# Sensors.net
KiCad netlist of a schematic drawn in Altium Designer
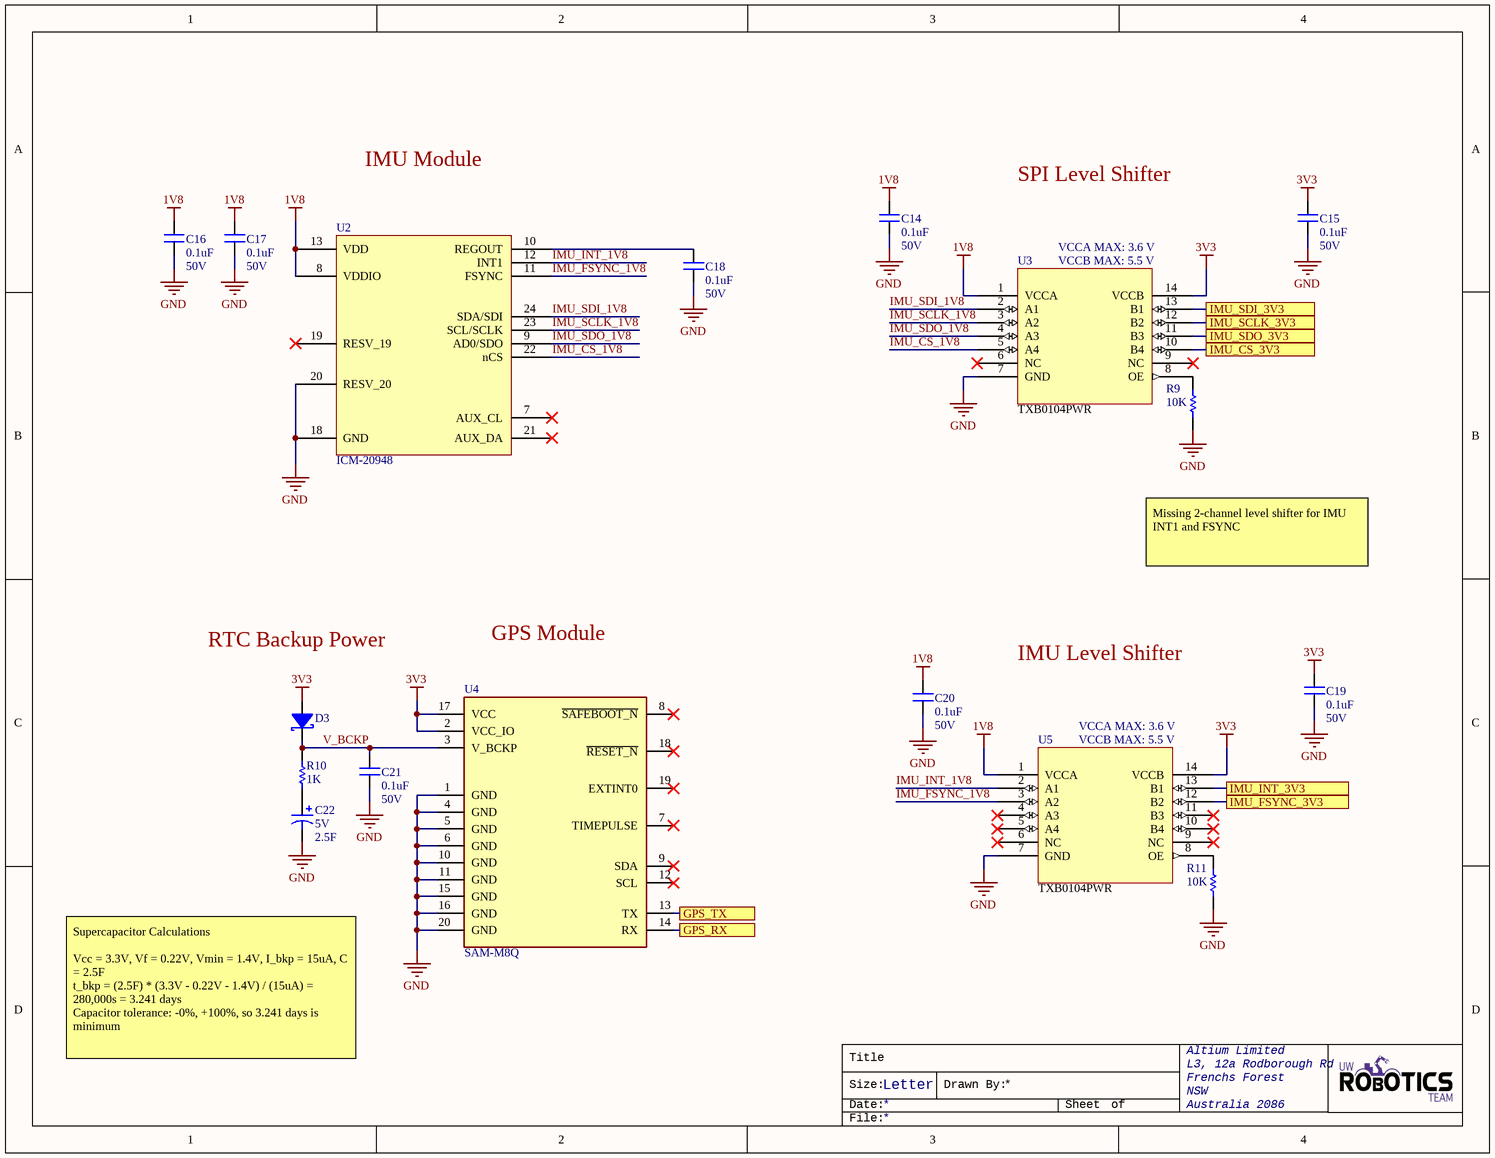
[diagram p0: Sensors.SchDoc]

(export (version "E")
  (design (tool "Eeschema 10.0.6"))
  (components
    (comp (ref "C14")
      (value "0.1uF")
      (footprint "CAPC2012X140N")
      (description "CAP CER 0.1UF 50V X7R 0805")
      (fields
        (field (name "TOLERANCE") "10%")
        (field (name "VOLTAGE RATING") "50V")
        (field (name "Comment") "CAP_0.1uF_50V_0805")
      )
      (libsource (lib "UWRT_Schematic_Library_2020") (part "CAP_0.1uF_50V_0805"))
    )
    (comp (ref "C15")
      (value "0.1uF")
      (footprint "CAPC2012X140N")
      (description "CAP CER 0.1UF 50V X7R 0805")
      (fields
        (field (name "TOLERANCE") "10%")
        (field (name "VOLTAGE RATING") "50V")
        (field (name "Comment") "CAP_0.1uF_50V_0805")
      )
      (libsource (lib "UWRT_Schematic_Library_2020") (part "CAP_0.1uF_50V_0805"))
    )
    (comp (ref "C16")
      (value "0.1uF")
      (footprint "CAPC2012X140N")
      (description "CAP CER 0.1UF 50V X7R 0805")
      (fields
        (field (name "TOLERANCE") "10%")
        (field (name "VOLTAGE RATING") "50V")
        (field (name "Comment") "CAP_0.1uF_50V_0805")
      )
      (libsource (lib "UWRT_Schematic_Library_2020") (part "CAP_0.1uF_50V_0805"))
    )
    (comp (ref "C17")
      (value "0.1uF")
      (footprint "CAPC2012X140N")
      (description "CAP CER 0.1UF 50V X7R 0805")
      (fields
        (field (name "TOLERANCE") "10%")
        (field (name "VOLTAGE RATING") "50V")
        (field (name "Comment") "CAP_0.1uF_50V_0805")
      )
      (libsource (lib "UWRT_Schematic_Library_2020") (part "CAP_0.1uF_50V_0805"))
    )
    (comp (ref "C18")
      (value "0.1uF")
      (footprint "CAPC2012X140N")
      (description "CAP CER 0.1UF 50V X7R 0805")
      (fields
        (field (name "TOLERANCE") "10%")
        (field (name "VOLTAGE RATING") "50V")
        (field (name "Comment") "CAP_0.1uF_50V_0805")
      )
      (libsource (lib "UWRT_Schematic_Library_2020") (part "CAP_0.1uF_50V_0805"))
    )
    (comp (ref "C19")
      (value "0.1uF")
      (footprint "CAPC2012X140N")
      (description "CAP CER 0.1UF 50V X7R 0805")
      (fields
        (field (name "TOLERANCE") "10%")
        (field (name "VOLTAGE RATING") "50V")
        (field (name "Comment") "CAP_0.1uF_50V_0805")
      )
      (libsource (lib "UWRT_Schematic_Library_2020") (part "CAP_0.1uF_50V_0805"))
    )
    (comp (ref "C20")
      (value "0.1uF")
      (footprint "CAPC2012X140N")
      (description "CAP CER 0.1UF 50V X7R 0805")
      (fields
        (field (name "TOLERANCE") "10%")
        (field (name "VOLTAGE RATING") "50V")
        (field (name "Comment") "CAP_0.1uF_50V_0805")
      )
      (libsource (lib "UWRT_Schematic_Library_2020") (part "CAP_0.1uF_50V_0805"))
    )
    (comp (ref "C21")
      (value "0.1uF")
      (footprint "CAPC2012X140N")
      (description "CAP CER 0.1UF 50V X7R 0805")
      (fields
        (field (name "TOLERANCE") "10%")
        (field (name "VOLTAGE RATING") "50V")
        (field (name "Comment") "CAP_0.1uF_50V_0805")
      )
      (libsource (lib "UWRT_Schematic_Library_2020") (part "CAP_0.1uF_50V_0805"))
    )
    (comp (ref "C22")
      (value "CAP_2.5F_5V")
      (description "CAP 2.5F 5V")
      (fields
        (field (name "TOLERANCE") "0%, +100%")
        (field (name "VOLTAGE RATING") "5V")
        (field (name "CAPACITANCE") "2.5F")
      )
      (libsource (lib "UWRT_Schematic_Library_2020") (part "CAP_2.5F_5V"))
    )
    (comp (ref "D3")
      (value "DIO_SCHOTTKY_30V_800mA")
      (footprint "DIO_CUS520,H3F")
      (description "DIODE SCHOTTKY 30V 800MA USC")
      (libsource (lib "UWRT_Schematic_Library_2020") (part "DIO_SCHOTTKY_30V_800mA"))
    )
    (comp (ref "R9")
      (value "10K")
      (footprint "RESC0603(1608)_N")
      (description "RES SMD 10K OHM 5% 1/10W 0603")
      (fields (field (name "TOLERANCE") "5%") (field (name "Comment") "RES_10K_0603"))
      (libsource (lib "UWRT_Schematic_Library_2020") (part "RES_10K_0603"))
    )
    (comp (ref "R10")
      (value "1K")
      (footprint "RESC0603(1608)_N")
      (description "RES SMD 1K OHM 5% 1/10W 0603")
      (fields (field (name "TOLERANCE") "5%") (field (name "Comment") "RES_1K_0603"))
      (libsource (lib "UWRT_Schematic_Library_2020") (part "RES_1K_0603"))
    )
    (comp (ref "R11")
      (value "10K")
      (footprint "RESC0603(1608)_N")
      (description "RES SMD 10K OHM 5% 1/10W 0603")
      (fields (field (name "TOLERANCE") "5%") (field (name "Comment") "RES_10K_0603"))
      (libsource (lib "UWRT_Schematic_Library_2020") (part "RES_10K_0603"))
    )
    (comp (ref "U2")
      (value "IC_9DOF_IMU")
      (footprint "ICM-20948")
      (description "IMU ACCEL/GYRO/COMPI2C/SPI 24QFN")
      (fields
        (field (name "MANUFACTURER") "TDK InvenSense")
        (field (name "MANUFACTURER PART NUMBER") "ICM-20948")
      )
      (libsource (lib "UWRT_Schematic_Library_2020") (part "IC_9DOF_IMU"))
    )
    (comp (ref "U3")
      (value "TXB0104PWR")
      (footprint "UWRT_Footprint_Library_2020:PW14")
      (fields
        (field (name "MANUFACTURER_PART_NUMBER") "TXB0104PWR")
        (field (name "GENERIC_PART_NUMBER") "TXB0104")
        (field (name "MANUFACTURER") "Texas Instruments")
        (field (name "VCCB MAX") "VCCB MAX: 5.5 V")
        (field (name "VCCA MAX") "VCCA MAX: 3.6 V")
      )
      (libsource (lib "UWRT_Schematic_Library_2020") (part "IC_4CH_LVL_SHIFTER"))
    )
    (comp (ref "U4")
      (value "SAM-M8Q")
      (description "Rf Rx Galileo 1.575GHZ/1.602GHZ")
      (libsource (lib "UWRT_Schematic_Library_2020") (part "SAM-M8Q"))
    )
    (comp (ref "U5")
      (value "TXB0104PWR")
      (footprint "UWRT_Footprint_Library_2020:PW14")
      (fields
        (field (name "MANUFACTURER_PART_NUMBER") "TXB0104PWR")
        (field (name "GENERIC_PART_NUMBER") "TXB0104")
        (field (name "MANUFACTURER") "Texas Instruments")
        (field (name "VCCB MAX") "VCCB MAX: 5.5 V")
        (field (name "VCCA MAX") "VCCA MAX: 3.6 V")
      )
      (libsource (lib "UWRT_Schematic_Library_2020") (part "IC_4CH_LVL_SHIFTER"))
    )
  )
  (nets
    (net (code "1") (name "/GPS_RX") (class "Default")
      (node (ref "U4") (pin "14") (pinfunction "RX_14") (pintype "passive"))
    )
    (net (code "2") (name "/GPS_TX") (class "Default")
      (node (ref "U4") (pin "13") (pinfunction "TX_13") (pintype "passive"))
    )
    (net (code "3") (name "/IMU_CS_1V8") (class "Default")
      (node (ref "U2") (pin "22") (pinfunction "nCS_22") (pintype "passive"))
      (node (ref "U3") (pin "5") (pinfunction "A4_5") (pintype "bidirectional"))
    )
    (net (code "4") (name "/IMU_CS_3V3") (class "Default")
      (node (ref "U3") (pin "10") (pinfunction "B4_10") (pintype "bidirectional"))
    )
    (net (code "5") (name "/IMU_FSYNC_1V8") (class "Default")
      (node (ref "U2") (pin "11") (pinfunction "FSYNC_11") (pintype "passive"))
      (node (ref "U5") (pin "3") (pinfunction "A2_3") (pintype "bidirectional"))
    )
    (net (code "6") (name "/IMU_FSYNC_3V3") (class "Default")
      (node (ref "U5") (pin "12") (pinfunction "B2_12") (pintype "bidirectional"))
    )
    (net (code "7") (name "/IMU_INT_1V8") (class "Default")
      (node (ref "U2") (pin "12") (pinfunction "INT1_12") (pintype "passive"))
      (node (ref "U5") (pin "2") (pinfunction "A1_2") (pintype "bidirectional"))
    )
    (net (code "8") (name "/IMU_INT_3V3") (class "Default")
      (node (ref "U5") (pin "13") (pinfunction "B1_13") (pintype "bidirectional"))
    )
    (net (code "9") (name "/IMU_SCLK_1V8") (class "Default")
      (node (ref "U2") (pin "23") (pinfunction "SCL/SCLK_23") (pintype "passive"))
      (node (ref "U3") (pin "3") (pinfunction "A2_3") (pintype "bidirectional"))
    )
    (net (code "10") (name "/IMU_SCLK_3V3") (class "Default")
      (node (ref "U3") (pin "12") (pinfunction "B2_12") (pintype "bidirectional"))
    )
    (net (code "11") (name "/IMU_SDI_1V8") (class "Default")
      (node (ref "U2") (pin "24") (pinfunction "SDA/SDI_24") (pintype "passive"))
      (node (ref "U3") (pin "2") (pinfunction "A1_2") (pintype "bidirectional"))
    )
    (net (code "12") (name "/IMU_SDI_3V3") (class "Default")
      (node (ref "U3") (pin "13") (pinfunction "B1_13") (pintype "bidirectional"))
    )
    (net (code "13") (name "/IMU_SDO_1V8") (class "Default")
      (node (ref "U2") (pin "9") (pinfunction "AD0/SDO_9") (pintype "passive"))
      (node (ref "U3") (pin "4") (pinfunction "A3_4") (pintype "bidirectional"))
    )
    (net (code "14") (name "/IMU_SDO_3V3") (class "Default")
      (node (ref "U3") (pin "11") (pinfunction "B3_11") (pintype "bidirectional"))
    )
    (net (code "15") (name "/V_BCKP") (class "Default")
      (node (ref "C21") (pin "2") (pinfunction "2_2") (pintype "passive"))
      (node (ref "D3") (pin "2") (pinfunction "Cathode_2") (pintype "passive"))
      (node (ref "R10") (pin "1") (pinfunction "1_1") (pintype "passive"))
      (node (ref "U4") (pin "3") (pinfunction "V_BCKP_3") (pintype "power_in"))
    )
    (net (code "16") (name "1V8") (class "Default")
      (node (ref "C14") (pin "2") (pinfunction "2_2") (pintype "passive"))
      (node (ref "C16") (pin "2") (pinfunction "2_2") (pintype "passive"))
      (node (ref "C17") (pin "2") (pinfunction "2_2") (pintype "passive"))
      (node (ref "C20") (pin "2") (pinfunction "2_2") (pintype "passive"))
      (node (ref "U2") (pin "13") (pinfunction "VDD_13") (pintype "passive"))
      (node (ref "U2") (pin "8") (pinfunction "VDDIO_8") (pintype "passive"))
      (node (ref "U3") (pin "1") (pinfunction "VCCA_1") (pintype "power_in"))
      (node (ref "U5") (pin "1") (pinfunction "VCCA_1") (pintype "power_in"))
    )
    (net (code "17") (name "3V3") (class "Default")
      (node (ref "C15") (pin "2") (pinfunction "2_2") (pintype "passive"))
      (node (ref "C19") (pin "2") (pinfunction "2_2") (pintype "passive"))
      (node (ref "D3") (pin "1") (pinfunction "Anode_1") (pintype "passive"))
      (node (ref "U3") (pin "14") (pinfunction "VCCB_14") (pintype "power_in"))
      (node (ref "U4") (pin "17") (pinfunction "VCC_17") (pintype "power_in"))
      (node (ref "U4") (pin "2") (pinfunction "VCC_IO_2") (pintype "power_in"))
      (node (ref "U5") (pin "14") (pinfunction "VCCB_14") (pintype "power_in"))
    )
    (net (code "18") (name "GND") (class "Default")
      (node (ref "C14") (pin "1") (pinfunction "1_1") (pintype "passive"))
      (node (ref "C15") (pin "1") (pinfunction "1_1") (pintype "passive"))
      (node (ref "C16") (pin "1") (pinfunction "1_1") (pintype "passive"))
      (node (ref "C17") (pin "1") (pinfunction "1_1") (pintype "passive"))
      (node (ref "C18") (pin "1") (pinfunction "1_1") (pintype "passive"))
      (node (ref "C19") (pin "1") (pinfunction "1_1") (pintype "passive"))
      (node (ref "C20") (pin "1") (pinfunction "1_1") (pintype "passive"))
      (node (ref "C21") (pin "1") (pinfunction "1_1") (pintype "passive"))
      (node (ref "C22") (pin "2") (pinfunction "2_2") (pintype "passive"))
      (node (ref "R11") (pin "2") (pinfunction "2_2") (pintype "passive"))
      (node (ref "R9") (pin "2") (pinfunction "2_2") (pintype "passive"))
      (node (ref "U2") (pin "18") (pinfunction "GND_18") (pintype "passive"))
      (node (ref "U2") (pin "20") (pinfunction "RESV_20_20") (pintype "passive"))
      (node (ref "U3") (pin "7") (pinfunction "GND_7") (pintype "power_in"))
      (node (ref "U4") (pin "1") (pinfunction "GND_1") (pintype "power_in"))
      (node (ref "U4") (pin "10") (pinfunction "GND_10") (pintype "power_in"))
      (node (ref "U4") (pin "11") (pinfunction "GND_11") (pintype "power_in"))
      (node (ref "U4") (pin "15") (pinfunction "GND_15") (pintype "power_in"))
      (node (ref "U4") (pin "16") (pinfunction "GND_16") (pintype "power_in"))
      (node (ref "U4") (pin "20") (pinfunction "GND_20") (pintype "power_in"))
      (node (ref "U4") (pin "4") (pinfunction "GND_4") (pintype "power_in"))
      (node (ref "U4") (pin "5") (pinfunction "GND_5") (pintype "power_in"))
      (node (ref "U4") (pin "6") (pinfunction "GND_6") (pintype "power_in"))
      (node (ref "U5") (pin "7") (pinfunction "GND_7") (pintype "power_in"))
    )
    (net (code "19") (name "Net-(C22-Pad1)") (class "Default")
      (node (ref "C22") (pin "1") (pinfunction "1_1") (pintype "passive"))
      (node (ref "R10") (pin "2") (pinfunction "2_2") (pintype "passive"))
    )
    (net (code "20") (name "Net-(U2-REGOUT)") (class "Default")
      (node (ref "C18") (pin "2") (pinfunction "2_2") (pintype "passive"))
      (node (ref "U2") (pin "10") (pinfunction "REGOUT_10") (pintype "passive"))
    )
    (net (code "21") (name "Net-(U3-OE)") (class "Default")
      (node (ref "R9") (pin "1") (pinfunction "1_1") (pintype "passive"))
      (node (ref "U3") (pin "8") (pinfunction "OE_8") (pintype "output"))
    )
    (net (code "22") (name "Net-(U5-OE)") (class "Default")
      (node (ref "R11") (pin "1") (pinfunction "1_1") (pintype "passive"))
      (node (ref "U5") (pin "8") (pinfunction "OE_8") (pintype "output"))
    )
    (net (code "23") (name "unconnected-(U2-AUX_CL-Pad7)") (class "Default")
      (node (ref "U2") (pin "7") (pinfunction "AUX_CL_7") (pintype "passive+no_connect"))
    )
    (net (code "24") (name "unconnected-(U2-AUX_DA-Pad21)") (class "Default")
      (node (ref "U2") (pin "21") (pinfunction "AUX_DA_21") (pintype "passive+no_connect"))
    )
    (net (code "25") (name "unconnected-(U2-RESV_19-Pad19)") (class "Default")
      (node (ref "U2") (pin "19") (pinfunction "RESV_19_19") (pintype "passive+no_connect"))
    )
    (net (code "26") (name "unconnected-(U3-NC-Pad6)") (class "Default")
      (node (ref "U3") (pin "6") (pinfunction "NC_6") (pintype "passive+no_connect"))
    )
    (net (code "27") (name "unconnected-(U3-NC-Pad9)") (class "Default")
      (node (ref "U3") (pin "9") (pinfunction "NC_9") (pintype "passive+no_connect"))
    )
    (net (code "28") (name "unconnected-(U4-EXTINT0-Pad19)") (class "Default")
      (node (ref "U4") (pin "19") (pinfunction "EXTINT0_19") (pintype "passive+no_connect"))
    )
    (net (code "29") (name "unconnected-(U4-SCL-Pad12)") (class "Default")
      (node (ref "U4") (pin "12") (pinfunction "SCL_12") (pintype "passive+no_connect"))
    )
    (net (code "30") (name "unconnected-(U4-SDA-Pad9)") (class "Default")
      (node (ref "U4") (pin "9") (pinfunction "SDA_9") (pintype "passive+no_connect"))
    )
    (net (code "31") (name "unconnected-(U4-TIMEPULSE-Pad7)") (class "Default")
      (node (ref "U4") (pin "7") (pinfunction "TIMEPULSE_7") (pintype "passive+no_connect"))
    )
    (net (code "32") (name "unconnected-(U4-~{RESET_N}-Pad18)") (class "Default")
      (node (ref "U4") (pin "18") (pinfunction "~{RESET_N}_18") (pintype "passive+no_connect"))
    )
    (net (code "33") (name "unconnected-(U4-~{SAFEBOOT_N}-Pad8)") (class "Default")
      (node (ref "U4") (pin "8") (pinfunction "~{SAFEBOOT_N}_8") (pintype "passive+no_connect"))
    )
    (net (code "34") (name "unconnected-(U5-A3-Pad4)") (class "Default")
      (node (ref "U5") (pin "4") (pinfunction "A3_4") (pintype "bidirectional+no_connect"))
    )
    (net (code "35") (name "unconnected-(U5-A4-Pad5)") (class "Default")
      (node (ref "U5") (pin "5") (pinfunction "A4_5") (pintype "bidirectional+no_connect"))
    )
    (net (code "36") (name "unconnected-(U5-B3-Pad11)") (class "Default")
      (node (ref "U5") (pin "11") (pinfunction "B3_11") (pintype "bidirectional+no_connect"))
    )
    (net (code "37") (name "unconnected-(U5-B4-Pad10)") (class "Default")
      (node (ref "U5") (pin "10") (pinfunction "B4_10") (pintype "bidirectional+no_connect"))
    )
    (net (code "38") (name "unconnected-(U5-NC-Pad6)") (class "Default")
      (node (ref "U5") (pin "6") (pinfunction "NC_6") (pintype "passive+no_connect"))
    )
    (net (code "39") (name "unconnected-(U5-NC-Pad9)") (class "Default")
      (node (ref "U5") (pin "9") (pinfunction "NC_9") (pintype "passive+no_connect"))
    )
  )
)
